# Sheet_Robo_Sumo.net
KiCad netlist of a schematic drawn in Altium Designer
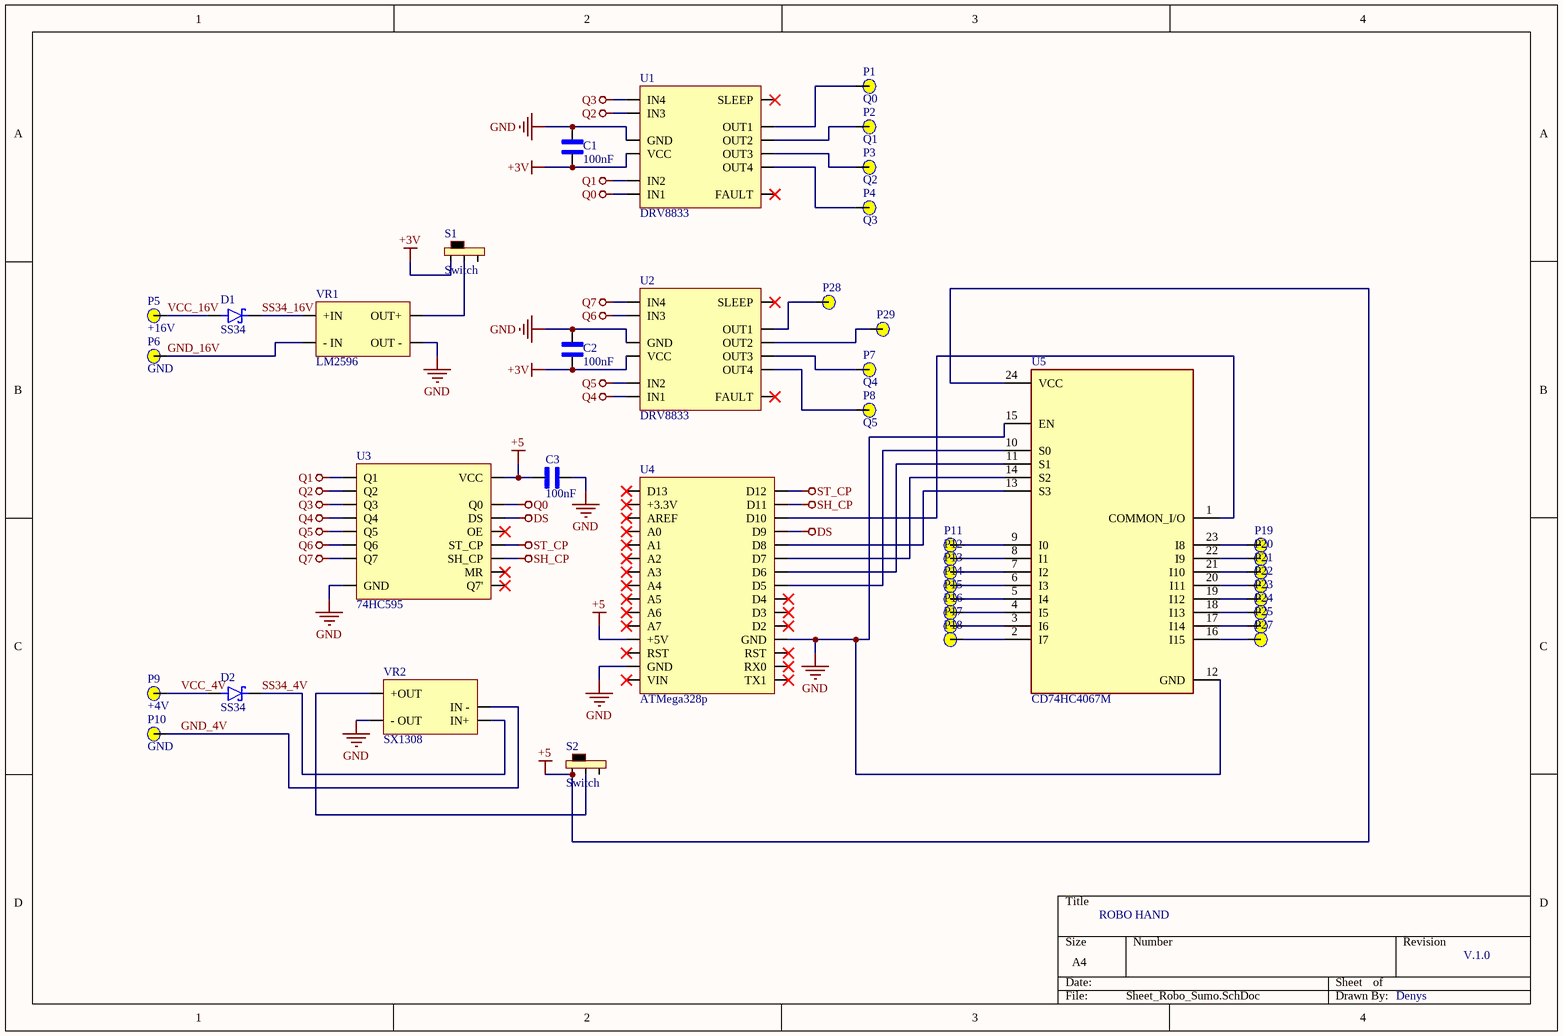
[diagram p0: Sheet_Robo_Sumo.SchDoc]

(export (version "E")
  (design (tool "Eeschema 10.0.6"))
  (components
    (comp (ref "C1")
      (value "100nF")
      (footprint "CAPC3216X180N")
      (description "Ceramic capacitor SMD 1206 100 nF 50 V 10 % Samsung Electro-Mechanics CL31B104KBCNNNC 4000 pc(s)")
      (fields (field (name "MP") "CL31B104KBCNNNC") (field (name "MF") "Samsung Electro-Mechanics"))
      (libsource (lib "") (part "C_1206_100nF_2"))
    )
    (comp (ref "C2")
      (value "100nF")
      (footprint "CAPC3216X180N")
      (description "Ceramic capacitor SMD 1206 100 nF 50 V 10 % Samsung Electro-Mechanics CL31B104KBCNNNC 4000 pc(s)")
      (fields (field (name "MP") "CL31B104KBCNNNC") (field (name "MF") "Samsung Electro-Mechanics"))
      (libsource (lib "С_1206_100nF") (part "C_1206_100nF"))
    )
    (comp (ref "C3")
      (value "100nF")
      (footprint "CAPC3216X180N")
      (description "Ceramic capacitor SMD 1206 100 nF 50 V 10 % Samsung Electro-Mechanics CL31B104KBCNNNC 4000 pc(s)")
      (fields (field (name "MP") "CL31B104KBCNNNC") (field (name "MF") "Samsung Electro-Mechanics"))
      (libsource (lib "") (part "C_1206_100nF_1"))
    )
    (comp (ref "D1")
      (value "SS34")
      (footprint "DIOM7959X265N")
      (description "SS34 - діод Шоттки")
      (fields (field (name "MF") "onsemi"))
      (libsource (lib "Sch_SS34") (part "Diode_SS34"))
    )
    (comp (ref "D2")
      (value "SS34")
      (footprint "DIOM7959X265N")
      (description "SS34 - діод Шоттки")
      (fields (field (name "MF") "onsemi"))
      (libsource (lib "Sch_SS34") (part "Diode_SS34"))
    )
    (comp (ref "P1") (value "Q0") (footprint "PCB_Pin_1") (libsource (lib "Sch_Pin_1") (part "PIN_1")))
    (comp (ref "P2") (value "Q1") (footprint "PCB_Pin_1") (libsource (lib "Sch_Pin_1") (part "PIN_1")))
    (comp (ref "P3") (value "Q2") (footprint "PCB_Pin_1") (libsource (lib "Sch_Pin_1") (part "PIN_1")))
    (comp (ref "P4") (value "Q3") (footprint "PCB_Pin_1") (libsource (lib "Sch_Pin_1") (part "PIN_1")))
    (comp (ref "P5") (value "+16V") (footprint "PCB_Pin_1") (libsource (lib "Sch_Pin_1") (part "PIN_1")))
    (comp (ref "P6") (value "GND") (footprint "PCB_Pin_1") (libsource (lib "Sch_Pin_1") (part "PIN_1")))
    (comp (ref "P7") (value "Q4") (footprint "PCB_Pin_1") (libsource (lib "Sch_Pin_1") (part "PIN_1")))
    (comp (ref "P8") (value "Q5") (footprint "PCB_Pin_1") (libsource (lib "Sch_Pin_1") (part "PIN_1")))
    (comp (ref "P9") (value "+4V") (footprint "PCB_Pin_1") (libsource (lib "Sch_Pin_1") (part "PIN_1")))
    (comp (ref "P10") (value "GND") (footprint "PCB_Pin_1") (libsource (lib "Sch_Pin_1") (part "PIN_1")))
    (comp (ref "P11") (value "~") (footprint "PCB_Pin_1") (libsource (lib "Sch_Pin_1") (part "PIN_1")))
    (comp (ref "P12") (value "~") (footprint "PCB_Pin_1") (libsource (lib "Sch_Pin_1") (part "PIN_1")))
    (comp (ref "P13") (value "~") (footprint "PCB_Pin_1") (libsource (lib "Sch_Pin_1") (part "PIN_1")))
    (comp (ref "P14") (value "~") (footprint "PCB_Pin_1") (libsource (lib "Sch_Pin_1") (part "PIN_1")))
    (comp (ref "P15") (value "~") (footprint "PCB_Pin_1") (libsource (lib "Sch_Pin_1") (part "PIN_1")))
    (comp (ref "P16") (value "~") (footprint "PCB_Pin_1") (libsource (lib "Sch_Pin_1") (part "PIN_1")))
    (comp (ref "P17") (value "~") (footprint "PCB_Pin_1") (libsource (lib "Sch_Pin_1") (part "PIN_1")))
    (comp (ref "P18") (value "~") (footprint "PCB_Pin_1") (libsource (lib "Sch_Pin_1") (part "PIN_1")))
    (comp (ref "P19") (value "~") (footprint "PCB_Pin_1") (libsource (lib "Sch_Pin_1") (part "PIN_1")))
    (comp (ref "P20") (value "~") (footprint "PCB_Pin_1") (libsource (lib "Sch_Pin_1") (part "PIN_1")))
    (comp (ref "P21") (value "~") (footprint "PCB_Pin_1") (libsource (lib "Sch_Pin_1") (part "PIN_1")))
    (comp (ref "P22") (value "~") (footprint "PCB_Pin_1") (libsource (lib "Sch_Pin_1") (part "PIN_1")))
    (comp (ref "P23") (value "~") (footprint "PCB_Pin_1") (libsource (lib "Sch_Pin_1") (part "PIN_1")))
    (comp (ref "P24") (value "~") (footprint "PCB_Pin_1") (libsource (lib "Sch_Pin_1") (part "PIN_1")))
    (comp (ref "P25") (value "~") (footprint "PCB_Pin_1") (libsource (lib "Sch_Pin_1") (part "PIN_1")))
    (comp (ref "P27") (value "~") (footprint "PCB_Pin_1") (libsource (lib "Sch_Pin_1") (part "PIN_1")))
    (comp (ref "P28") (value "PIN_1") (footprint "PCB_Pin_1") (libsource (lib "Sch_Pin_1") (part "PIN_1")))
    (comp (ref "P29") (value "PIN_1") (footprint "PCB_Pin_1") (libsource (lib "Sch_Pin_1") (part "PIN_1")))
    (comp (ref "S1") (value "Switch") (footprint "Switcth") (libsource (lib "Switch") (part "Switch")))
    (comp (ref "S2") (value "Switch") (footprint "Switcth") (libsource (lib "Switch") (part "Switch")))
    (comp (ref "U1")
      (value "DRV8833")
      (footprint "PCB_DRV8833")
      (description "Драйвер крокового/колекторних двигунів DRV8833")
      (libsource (lib "Sch_DRV8833") (part "Motor Driver"))
    )
    (comp (ref "U2")
      (value "DRV8833")
      (footprint "PCB_DRV8833")
      (description "Драйвер крокового/колекторних двигунів DRV8833")
      (libsource (lib "Sch_DRV8833") (part "Motor Driver"))
    )
    (comp (ref "U3")
      (value "74HC595")
      (footprint "PCB_74HC595_Footprint")
      (description "SN74HC595N - вихідний зсувний регістр 74HC595")
      (libsource (lib "Sch_74HC595") (part "SCS-16"))
    )
    (comp (ref "U4")
      (value "ATMega328p")
      (footprint "PCB_ATMega328p")
      (description "DCCduino Nano CH340 - аналог Arduino Nano v3.0 TYPE C")
      (libsource (lib "Sch_ATMega328p") (part "Arduino Nano"))
    )
    (comp (ref "U5")
      (value "CD74HC4067M")
      (footprint "CD74HC4067M")
      (description "5-V, 16:1, 1-channel analog multiplexer")
      (libsource (lib "CD74HC4067M") (part "CD74HC4067M"))
    )
    (comp (ref "VR1")
      (value "LM2596")
      (footprint "DC-DC Step-Down Footprint")
      (description "DC-DC конвертер знижуючий 4.5...40В на 1.5...35В на LM2596")
      (libsource (lib "Sch_LM2596") (part "DC-DC Step-Down"))
    )
    (comp (ref "VR2")
      (value "SX1308")
      (footprint "DC-DC Step-Up Footprint")
      (description "Mini DC-DC конвертер підвищує 2.5..10В 5В/8В/9В/12В на SX1308")
      (libsource (lib "Sch_SX1308") (part "DC-DC Step-Up"))
    )
  )
  (nets
    (net (code "1") (name "+3V") (class "Default")
      (node (ref "C1") (pin "2") (pinfunction "2_2") (pintype "passive"))
      (node (ref "C2") (pin "1") (pinfunction "1_1") (pintype "passive"))
      (node (ref "S1") (pin "0") (pinfunction "Out1_0") (pintype "passive"))
      (node (ref "U1") (pin "2") (pinfunction "VCC_2") (pintype "power_in"))
      (node (ref "U2") (pin "2") (pinfunction "VCC_2") (pintype "power_in"))
    )
    (net (code "2") (name "+5") (class "Default")
      (node (ref "C3") (pin "2") (pinfunction "2_2") (pintype "passive"))
      (node (ref "S2") (pin "0") (pinfunction "Out1_0") (pintype "passive"))
      (node (ref "U3") (pin "8") (pinfunction "VCC_8") (pintype "power_in"))
      (node (ref "U4") (pin "3") (pinfunction "+5V_3") (pintype "passive"))
      (node (ref "U5") (pin "24") (pinfunction "VCC_24") (pintype "power_in"))
    )
    (net (code "3") (name "/GND_4V") (class "Default")
      (node (ref "P10") (pin "0") (pinfunction "Pin_0") (pintype "passive"))
      (node (ref "VR2") (pin "2") (pinfunction "IN_-_2") (pintype "power_in"))
    )
    (net (code "4") (name "/GND_16V") (class "Default")
      (node (ref "P6") (pin "0") (pinfunction "Pin_0") (pintype "passive"))
      (node (ref "VR1") (pin "0") (pinfunction "-_IN_0") (pintype "power_in"))
    )
    (net (code "5") (name "/SS34_4V") (class "Default")
      (node (ref "D2") (pin "C") (pinfunction "K_C") (pintype "passive"))
      (node (ref "VR2") (pin "3") (pinfunction "IN+_3") (pintype "power_in"))
    )
    (net (code "6") (name "/SS34_16V") (class "Default")
      (node (ref "D1") (pin "C") (pinfunction "K_C") (pintype "passive"))
      (node (ref "VR1") (pin "1") (pinfunction "+IN_1") (pintype "power_in"))
    )
    (net (code "7") (name "/VCC_4V") (class "Default")
      (node (ref "D2") (pin "A") (pinfunction "A_A") (pintype "passive"))
      (node (ref "P9") (pin "0") (pinfunction "Pin_0") (pintype "passive"))
    )
    (net (code "8") (name "/VCC_16V") (class "Default")
      (node (ref "D1") (pin "A") (pinfunction "A_A") (pintype "passive"))
      (node (ref "P5") (pin "0") (pinfunction "Pin_0") (pintype "passive"))
    )
    (net (code "9") (name "DS") (class "Default")
      (node (ref "U3") (pin "10") (pinfunction "DS_10") (pintype "passive"))
      (node (ref "U4") (pin "18") (pinfunction "D9_18") (pintype "passive"))
    )
    (net (code "10") (name "GND") (class "Default")
      (node (ref "C1") (pin "1") (pinfunction "1_1") (pintype "passive"))
      (node (ref "C2") (pin "2") (pinfunction "2_2") (pintype "passive"))
      (node (ref "C3") (pin "1") (pinfunction "1_1") (pintype "passive"))
      (node (ref "U1") (pin "3") (pinfunction "GND_3") (pintype "power_in"))
      (node (ref "U2") (pin "3") (pinfunction "GND_3") (pintype "power_in"))
      (node (ref "U3") (pin "0") (pinfunction "GND_0") (pintype "power_in"))
      (node (ref "U4") (pin "1") (pinfunction "GND_1") (pintype "passive"))
      (node (ref "U4") (pin "26") (pinfunction "GND_26") (pintype "passive"))
      (node (ref "U5") (pin "12") (pinfunction "GND_12") (pintype "power_in"))
      (node (ref "U5") (pin "15") (pinfunction "EN_15") (pintype "power_in"))
      (node (ref "VR1") (pin "3") (pinfunction "OUT_-_3") (pintype "power_in"))
      (node (ref "VR2") (pin "0") (pinfunction "-_OUT_0") (pintype "power_in"))
    )
    (net (code "11") (name "Net-(P1-Pin)") (class "Default")
      (node (ref "P1") (pin "0") (pinfunction "Pin_0") (pintype "passive"))
      (node (ref "U1") (pin "7") (pinfunction "OUT1_7") (pintype "passive"))
    )
    (net (code "12") (name "Net-(P2-Pin)") (class "Default")
      (node (ref "P2") (pin "0") (pinfunction "Pin_0") (pintype "passive"))
      (node (ref "U1") (pin "8") (pinfunction "OUT2_8") (pintype "passive"))
    )
    (net (code "13") (name "Net-(P3-Pin)") (class "Default")
      (node (ref "P3") (pin "0") (pinfunction "Pin_0") (pintype "passive"))
      (node (ref "U1") (pin "9") (pinfunction "OUT3_9") (pintype "passive"))
    )
    (net (code "14") (name "Net-(P4-Pin)") (class "Default")
      (node (ref "P4") (pin "0") (pinfunction "Pin_0") (pintype "passive"))
      (node (ref "U1") (pin "10") (pinfunction "OUT4_10") (pintype "passive"))
    )
    (net (code "15") (name "Net-(P7-Pin)") (class "Default")
      (node (ref "P7") (pin "0") (pinfunction "Pin_0") (pintype "passive"))
      (node (ref "U2") (pin "9") (pinfunction "OUT3_9") (pintype "passive"))
    )
    (net (code "16") (name "Net-(P8-Pin)") (class "Default")
      (node (ref "P8") (pin "0") (pinfunction "Pin_0") (pintype "passive"))
      (node (ref "U2") (pin "10") (pinfunction "OUT4_10") (pintype "passive"))
    )
    (net (code "17") (name "Net-(P11-Pin)") (class "Default")
      (node (ref "P11") (pin "0") (pinfunction "Pin_0") (pintype "passive"))
      (node (ref "U5") (pin "9") (pinfunction "I0_9") (pintype "power_in"))
    )
    (net (code "18") (name "Net-(P12-Pin)") (class "Default")
      (node (ref "P12") (pin "0") (pinfunction "Pin_0") (pintype "passive"))
      (node (ref "U5") (pin "8") (pinfunction "I1_8") (pintype "power_in"))
    )
    (net (code "19") (name "Net-(P13-Pin)") (class "Default")
      (node (ref "P13") (pin "0") (pinfunction "Pin_0") (pintype "passive"))
      (node (ref "U5") (pin "7") (pinfunction "I2_7") (pintype "power_in"))
    )
    (net (code "20") (name "Net-(P14-Pin)") (class "Default")
      (node (ref "P14") (pin "0") (pinfunction "Pin_0") (pintype "passive"))
      (node (ref "U5") (pin "6") (pinfunction "I3_6") (pintype "power_in"))
    )
    (net (code "21") (name "Net-(P15-Pin)") (class "Default")
      (node (ref "P15") (pin "0") (pinfunction "Pin_0") (pintype "passive"))
      (node (ref "U5") (pin "5") (pinfunction "I4_5") (pintype "power_in"))
    )
    (net (code "22") (name "Net-(P16-Pin)") (class "Default")
      (node (ref "P16") (pin "0") (pinfunction "Pin_0") (pintype "passive"))
      (node (ref "U5") (pin "4") (pinfunction "I5_4") (pintype "power_in"))
    )
    (net (code "23") (name "Net-(P17-Pin)") (class "Default")
      (node (ref "P17") (pin "0") (pinfunction "Pin_0") (pintype "passive"))
      (node (ref "U5") (pin "3") (pinfunction "I6_3") (pintype "power_in"))
    )
    (net (code "24") (name "Net-(P18-Pin)") (class "Default")
      (node (ref "P18") (pin "0") (pinfunction "Pin_0") (pintype "passive"))
      (node (ref "U5") (pin "2") (pinfunction "I7_2") (pintype "power_in"))
    )
    (net (code "25") (name "Net-(P19-Pin)") (class "Default")
      (node (ref "P19") (pin "0") (pinfunction "Pin_0") (pintype "passive"))
      (node (ref "U5") (pin "23") (pinfunction "I8_23") (pintype "power_in"))
    )
    (net (code "26") (name "Net-(P20-Pin)") (class "Default")
      (node (ref "P20") (pin "0") (pinfunction "Pin_0") (pintype "passive"))
      (node (ref "U5") (pin "22") (pinfunction "I9_22") (pintype "power_in"))
    )
    (net (code "27") (name "Net-(P21-Pin)") (class "Default")
      (node (ref "P21") (pin "0") (pinfunction "Pin_0") (pintype "passive"))
      (node (ref "U5") (pin "21") (pinfunction "I10_21") (pintype "power_in"))
    )
    (net (code "28") (name "Net-(P22-Pin)") (class "Default")
      (node (ref "P22") (pin "0") (pinfunction "Pin_0") (pintype "passive"))
      (node (ref "U5") (pin "20") (pinfunction "I11_20") (pintype "power_in"))
    )
    (net (code "29") (name "Net-(P23-Pin)") (class "Default")
      (node (ref "P23") (pin "0") (pinfunction "Pin_0") (pintype "passive"))
      (node (ref "U5") (pin "19") (pinfunction "I12_19") (pintype "power_in"))
    )
    (net (code "30") (name "Net-(P24-Pin)") (class "Default")
      (node (ref "P24") (pin "0") (pinfunction "Pin_0") (pintype "passive"))
      (node (ref "U5") (pin "18") (pinfunction "I13_18") (pintype "power_in"))
    )
    (net (code "31") (name "Net-(P25-Pin)") (class "Default")
      (node (ref "P25") (pin "0") (pinfunction "Pin_0") (pintype "passive"))
      (node (ref "U5") (pin "17") (pinfunction "I14_17") (pintype "power_in"))
    )
    (net (code "32") (name "Net-(P27-Pin)") (class "Default")
      (node (ref "P27") (pin "0") (pinfunction "Pin_0") (pintype "passive"))
      (node (ref "U5") (pin "16") (pinfunction "I15_16") (pintype "power_in"))
    )
    (net (code "33") (name "Net-(P28-Pin)") (class "Default")
      (node (ref "P28") (pin "0") (pinfunction "Pin_0") (pintype "passive"))
      (node (ref "U2") (pin "7") (pinfunction "OUT1_7") (pintype "passive"))
    )
    (net (code "34") (name "Net-(P29-Pin)") (class "Default")
      (node (ref "P29") (pin "0") (pinfunction "Pin_0") (pintype "passive"))
      (node (ref "U2") (pin "8") (pinfunction "OUT2_8") (pintype "passive"))
    )
    (net (code "35") (name "Net-(S1-In)") (class "Default")
      (node (ref "S1") (pin "1") (pinfunction "In_1") (pintype "passive"))
      (node (ref "VR1") (pin "2") (pinfunction "OUT+_2") (pintype "power_in"))
    )
    (net (code "36") (name "Net-(S2-In)") (class "Default")
      (node (ref "S2") (pin "1") (pinfunction "In_1") (pintype "passive"))
      (node (ref "VR2") (pin "1") (pinfunction "+OUT_1") (pintype "power_in"))
    )
    (net (code "37") (name "Net-(U4-D5)") (class "Default")
      (node (ref "U4") (pin "22") (pinfunction "D5_22") (pintype "passive"))
      (node (ref "U5") (pin "10") (pinfunction "S0_10") (pintype "power_in"))
    )
    (net (code "38") (name "Net-(U4-D6)") (class "Default")
      (node (ref "U4") (pin "21") (pinfunction "D6_21") (pintype "passive"))
      (node (ref "U5") (pin "11") (pinfunction "S1_11") (pintype "power_in"))
    )
    (net (code "39") (name "Net-(U4-D7)") (class "Default")
      (node (ref "U4") (pin "20") (pinfunction "D7_20") (pintype "passive"))
      (node (ref "U5") (pin "14") (pinfunction "S2_14") (pintype "power_in"))
    )
    (net (code "40") (name "Net-(U4-D8)") (class "Default")
      (node (ref "U4") (pin "19") (pinfunction "D8_19") (pintype "passive"))
      (node (ref "U5") (pin "13") (pinfunction "S3_13") (pintype "power_in"))
    )
    (net (code "41") (name "Net-(U4-D10)") (class "Default")
      (node (ref "U4") (pin "17") (pinfunction "D10_17") (pintype "passive"))
      (node (ref "U5") (pin "1") (pinfunction "COMMON_I/O_1") (pintype "power_in"))
    )
    (net (code "42") (name "Q0") (class "Default")
      (node (ref "U1") (pin "0") (pinfunction "IN1_0") (pintype "passive"))
      (node (ref "U3") (pin "9") (pinfunction "Q0_9") (pintype "passive"))
    )
    (net (code "43") (name "Q1") (class "Default")
      (node (ref "U1") (pin "1") (pinfunction "IN2_1") (pintype "passive"))
      (node (ref "U3") (pin "7") (pinfunction "Q1_7") (pintype "passive"))
    )
    (net (code "44") (name "Q2") (class "Default")
      (node (ref "U1") (pin "4") (pinfunction "IN3_4") (pintype "passive"))
      (node (ref "U3") (pin "6") (pinfunction "Q2_6") (pintype "passive"))
    )
    (net (code "45") (name "Q3") (class "Default")
      (node (ref "U1") (pin "5") (pinfunction "IN4_5") (pintype "passive"))
      (node (ref "U3") (pin "5") (pinfunction "Q3_5") (pintype "passive"))
    )
    (net (code "46") (name "Q4") (class "Default")
      (node (ref "U2") (pin "0") (pinfunction "IN1_0") (pintype "passive"))
      (node (ref "U3") (pin "4") (pinfunction "Q4_4") (pintype "passive"))
    )
    (net (code "47") (name "Q5") (class "Default")
      (node (ref "U2") (pin "1") (pinfunction "IN2_1") (pintype "passive"))
      (node (ref "U3") (pin "3") (pinfunction "Q5_3") (pintype "passive"))
    )
    (net (code "48") (name "Q6") (class "Default")
      (node (ref "U2") (pin "4") (pinfunction "IN3_4") (pintype "passive"))
      (node (ref "U3") (pin "2") (pinfunction "Q6_2") (pintype "passive"))
    )
    (net (code "49") (name "Q7") (class "Default")
      (node (ref "U2") (pin "5") (pinfunction "IN4_5") (pintype "passive"))
      (node (ref "U3") (pin "1") (pinfunction "Q7_1") (pintype "passive"))
    )
    (net (code "50") (name "SH_CP") (class "Default")
      (node (ref "U3") (pin "13") (pinfunction "SH_CP_13") (pintype "passive"))
      (node (ref "U4") (pin "16") (pinfunction "D11_16") (pintype "passive"))
    )
    (net (code "51") (name "ST_CP") (class "Default")
      (node (ref "U3") (pin "12") (pinfunction "ST_CP_12") (pintype "passive"))
      (node (ref "U4") (pin "15") (pinfunction "D12_15") (pintype "passive"))
    )
    (net (code "52") (name "unconnected-(S1-Out2-Pad2)") (class "Default")
      (node (ref "S1") (pin "2") (pinfunction "Out2_2") (pintype "passive"))
    )
    (net (code "53") (name "unconnected-(S2-Out2-Pad2)") (class "Default")
      (node (ref "S2") (pin "2") (pinfunction "Out2_2") (pintype "passive"))
    )
    (net (code "54") (name "unconnected-(U1-FAULT-Pad11)") (class "Default")
      (node (ref "U1") (pin "11") (pinfunction "FAULT_11") (pintype "passive+no_connect"))
    )
    (net (code "55") (name "unconnected-(U1-SLEEP-Pad6)") (class "Default")
      (node (ref "U1") (pin "6") (pinfunction "SLEEP_6") (pintype "passive+no_connect"))
    )
    (net (code "56") (name "unconnected-(U2-FAULT-Pad11)") (class "Default")
      (node (ref "U2") (pin "11") (pinfunction "FAULT_11") (pintype "passive+no_connect"))
    )
    (net (code "57") (name "unconnected-(U2-SLEEP-Pad6)") (class "Default")
      (node (ref "U2") (pin "6") (pinfunction "SLEEP_6") (pintype "passive+no_connect"))
    )
    (net (code "58") (name "unconnected-(U3-MR-Pad14)") (class "Default")
      (node (ref "U3") (pin "14") (pinfunction "MR_14") (pintype "passive+no_connect"))
    )
    (net (code "59") (name "unconnected-(U3-OE-Pad11)") (class "Default")
      (node (ref "U3") (pin "11") (pinfunction "OE_11") (pintype "passive+no_connect"))
    )
    (net (code "60") (name "unconnected-(U3-Q7'-Pad15)") (class "Default")
      (node (ref "U3") (pin "15") (pinfunction "Q7'_15") (pintype "passive+no_connect"))
    )
    (net (code "61") (name "unconnected-(U4-+3.3V-Pad13)") (class "Default")
      (node (ref "U4") (pin "13") (pinfunction "+3.3V_13") (pintype "passive+no_connect"))
    )
    (net (code "62") (name "unconnected-(U4-A0-Pad11)") (class "Default")
      (node (ref "U4") (pin "11") (pinfunction "A0_11") (pintype "passive+no_connect"))
    )
    (net (code "63") (name "unconnected-(U4-A1-Pad10)") (class "Default")
      (node (ref "U4") (pin "10") (pinfunction "A1_10") (pintype "passive+no_connect"))
    )
    (net (code "64") (name "unconnected-(U4-A2-Pad9)") (class "Default")
      (node (ref "U4") (pin "9") (pinfunction "A2_9") (pintype "passive+no_connect"))
    )
    (net (code "65") (name "unconnected-(U4-A3-Pad8)") (class "Default")
      (node (ref "U4") (pin "8") (pinfunction "A3_8") (pintype "passive+no_connect"))
    )
    (net (code "66") (name "unconnected-(U4-A4-Pad7)") (class "Default")
      (node (ref "U4") (pin "7") (pinfunction "A4_7") (pintype "passive+no_connect"))
    )
    (net (code "67") (name "unconnected-(U4-A5-Pad6)") (class "Default")
      (node (ref "U4") (pin "6") (pinfunction "A5_6") (pintype "passive+no_connect"))
    )
    (net (code "68") (name "unconnected-(U4-A6-Pad5)") (class "Default")
      (node (ref "U4") (pin "5") (pinfunction "A6_5") (pintype "passive+no_connect"))
    )
    (net (code "69") (name "unconnected-(U4-A7-Pad4)") (class "Default")
      (node (ref "U4") (pin "4") (pinfunction "A7_4") (pintype "passive+no_connect"))
    )
    (net (code "70") (name "unconnected-(U4-AREF-Pad12)") (class "Default")
      (node (ref "U4") (pin "12") (pinfunction "AREF_12") (pintype "passive+no_connect"))
    )
    (net (code "71") (name "unconnected-(U4-D2-Pad25)") (class "Default")
      (node (ref "U4") (pin "25") (pinfunction "D2_25") (pintype "passive+no_connect"))
    )
    (net (code "72") (name "unconnected-(U4-D3-Pad24)") (class "Default")
      (node (ref "U4") (pin "24") (pinfunction "D3_24") (pintype "passive+no_connect"))
    )
    (net (code "73") (name "unconnected-(U4-D4-Pad23)") (class "Default")
      (node (ref "U4") (pin "23") (pinfunction "D4_23") (pintype "passive+no_connect"))
    )
    (net (code "74") (name "unconnected-(U4-D13-Pad14)") (class "Default")
      (node (ref "U4") (pin "14") (pinfunction "D13_14") (pintype "passive+no_connect"))
    )
    (net (code "75") (name "unconnected-(U4-RST-Pad2)") (class "Default")
      (node (ref "U4") (pin "2") (pinfunction "RST_2") (pintype "passive+no_connect"))
    )
    (net (code "76") (name "unconnected-(U4-RST-Pad27)") (class "Default")
      (node (ref "U4") (pin "27") (pinfunction "RST_27") (pintype "passive+no_connect"))
    )
    (net (code "77") (name "unconnected-(U4-RX0-Pad28)") (class "Default")
      (node (ref "U4") (pin "28") (pinfunction "RX0_28") (pintype "passive+no_connect"))
    )
    (net (code "78") (name "unconnected-(U4-TX1-Pad29)") (class "Default")
      (node (ref "U4") (pin "29") (pinfunction "TX1_29") (pintype "passive+no_connect"))
    )
    (net (code "79") (name "unconnected-(U4-VIN-Pad0)") (class "Default")
      (node (ref "U4") (pin "0") (pinfunction "VIN_0") (pintype "passive+no_connect"))
    )
  )
)
